# bluetooth_RGB.net
KiCad netlist of a schematic drawn in EAGLE
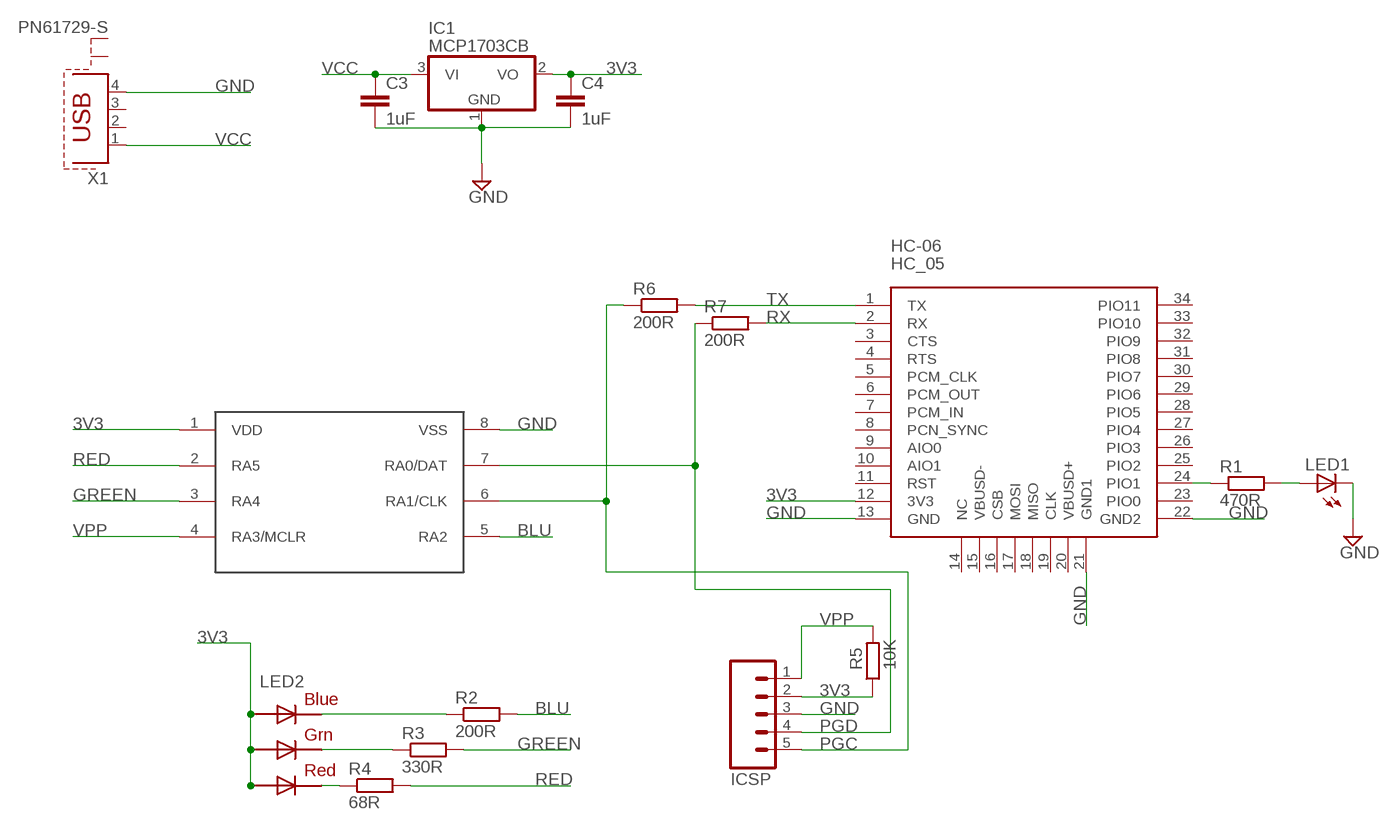
[diagram p0: schematic, sheet 1]

(export (version "E")
  (design (tool "Eeschema 10.0.6"))
  (components
    (comp (ref "C3")
      (value "1uF")
      (footprint "eagle-import:0805")
      (libsource (lib "eagle-import") (part "CAP0805"))
    )
    (comp (ref "C4")
      (value "1uF")
      (footprint "eagle-import:0805")
      (libsource (lib "eagle-import") (part "CAP0805"))
    )
    (comp (ref "HC-06")
      (value "HC_05")
      (footprint "eagle-import:BLUETOOTH_SMD")
      (libsource (lib "eagle-import") (part "HC_05"))
    )
    (comp (ref "IC1")
      (value "MCP1703CB")
      (footprint "eagle-import:SOT23")
      (libsource (lib "eagle-import") (part "MCP1703CB"))
    )
    (comp (ref "ICSP")
      (value "M05PTH")
      (footprint "eagle-import:1X05")
      (libsource (lib "eagle-import") (part "M05PTH"))
    )
    (comp (ref "LED1")
      (value "LEDCHIPLED_0805")
      (footprint "eagle-import:CHIPLED_0805")
      (libsource (lib "eagle-import") (part "LEDCHIPLED_0805"))
    )
    (comp (ref "LED2")
      (value "RGBLED5050")
      (footprint "eagle-import:RGBLED5050")
      (libsource (lib "eagle-import") (part "RGBLED5050"))
    )
    (comp (ref "R1")
      (value "470R")
      (footprint "eagle-import:M0805")
      (libsource (lib "eagle-import") (part "R-EU_M0805"))
    )
    (comp (ref "R2")
      (value "200R")
      (footprint "eagle-import:M0805")
      (libsource (lib "eagle-import") (part "R-EU_M0805"))
    )
    (comp (ref "R3")
      (value "330R")
      (footprint "eagle-import:M0805")
      (libsource (lib "eagle-import") (part "R-EU_M0805"))
    )
    (comp (ref "R4")
      (value "68R")
      (footprint "eagle-import:M0805")
      (libsource (lib "eagle-import") (part "R-EU_M0805"))
    )
    (comp (ref "R5")
      (value "10K")
      (footprint "eagle-import:M0805")
      (libsource (lib "eagle-import") (part "R-EU_M0805"))
    )
    (comp (ref "R6")
      (value "200R")
      (footprint "eagle-import:R0805")
      (libsource (lib "eagle-import") (part "R-EU_R0805"))
    )
    (comp (ref "R7")
      (value "200R")
      (footprint "eagle-import:R0805")
      (libsource (lib "eagle-import") (part "R-EU_R0805"))
    )
    (comp (ref "U2")
      (value "PIC12F1572")
      (footprint "eagle-import:MSOP8")
      (libsource (lib "eagle-import") (part "PIC12F1572"))
    )
    (comp (ref "X1")
      (value "PN61729-S")
      (footprint "eagle-import:PN61729-S")
      (libsource (lib "eagle-import") (part "PN61729-S"))
    )
  )
  (nets
    (net (code "1") (name "/3V3") (class "Default")
      (node (ref "C4") (pin "1") (pinfunction "1_1") (pintype "passive"))
      (node (ref "HC-06") (pin "12") (pinfunction "3V3_12") (pintype "bidirectional"))
      (node (ref "IC1") (pin "2") (pinfunction "VO_2") (pintype "passive"))
      (node (ref "ICSP") (pin "2") (pinfunction "2_2") (pintype "passive"))
      (node (ref "LED2") (pin "1") (pinfunction "GREEN_A_1") (pintype "bidirectional"))
      (node (ref "LED2") (pin "2") (pinfunction "RED_A_2") (pintype "bidirectional"))
      (node (ref "LED2") (pin "3") (pinfunction "BLUE_A_3") (pintype "bidirectional"))
      (node (ref "R5") (pin "1") (pinfunction "1_1") (pintype "passive"))
      (node (ref "U2") (pin "1") (pinfunction "VDD_1") (pintype "bidirectional"))
    )
    (net (code "2") (name "/BLU") (class "Default")
      (node (ref "R2") (pin "2") (pinfunction "2_2") (pintype "passive"))
      (node (ref "U2") (pin "5") (pinfunction "RA2_5") (pintype "bidirectional"))
    )
    (net (code "3") (name "/GREEN") (class "Default")
      (node (ref "R3") (pin "2") (pinfunction "2_2") (pintype "passive"))
      (node (ref "U2") (pin "3") (pinfunction "RA4_3") (pintype "bidirectional"))
    )
    (net (code "4") (name "/PGC") (class "Default")
      (node (ref "ICSP") (pin "5") (pinfunction "5_5") (pintype "passive"))
      (node (ref "R6") (pin "1") (pinfunction "1_1") (pintype "passive"))
      (node (ref "U2") (pin "6") (pinfunction "RA1/CLK_6") (pintype "bidirectional"))
    )
    (net (code "5") (name "/PGD") (class "Default")
      (node (ref "ICSP") (pin "4") (pinfunction "4_4") (pintype "passive"))
      (node (ref "R7") (pin "1") (pinfunction "1_1") (pintype "passive"))
      (node (ref "U2") (pin "7") (pinfunction "RA0/DAT_7") (pintype "bidirectional"))
    )
    (net (code "6") (name "/RED") (class "Default")
      (node (ref "R4") (pin "2") (pinfunction "2_2") (pintype "passive"))
      (node (ref "U2") (pin "2") (pinfunction "RA5_2") (pintype "bidirectional"))
    )
    (net (code "7") (name "/RX") (class "Default")
      (node (ref "HC-06") (pin "2") (pinfunction "RX_2") (pintype "bidirectional"))
      (node (ref "R7") (pin "2") (pinfunction "2_2") (pintype "passive"))
    )
    (net (code "8") (name "/TX") (class "Default")
      (node (ref "HC-06") (pin "1") (pinfunction "TX_1") (pintype "bidirectional"))
      (node (ref "R6") (pin "2") (pinfunction "2_2") (pintype "passive"))
    )
    (net (code "9") (name "/VCC") (class "Default")
      (node (ref "C3") (pin "1") (pinfunction "1_1") (pintype "passive"))
      (node (ref "IC1") (pin "3") (pinfunction "VI_3") (pintype "input"))
      (node (ref "X1") (pin "1") (pinfunction "1_1") (pintype "passive"))
    )
    (net (code "10") (name "/VPP") (class "Default")
      (node (ref "ICSP") (pin "1") (pinfunction "1_1") (pintype "passive"))
      (node (ref "R5") (pin "2") (pinfunction "2_2") (pintype "passive"))
      (node (ref "U2") (pin "4") (pinfunction "RA3/MCLR_4") (pintype "bidirectional"))
    )
    (net (code "11") (name "GND") (class "Default")
      (node (ref "C3") (pin "2") (pinfunction "2_2") (pintype "passive"))
      (node (ref "C4") (pin "2") (pinfunction "2_2") (pintype "passive"))
      (node (ref "HC-06") (pin "13") (pinfunction "GND_13") (pintype "bidirectional"))
      (node (ref "HC-06") (pin "21") (pinfunction "GND1_21") (pintype "bidirectional"))
      (node (ref "HC-06") (pin "22") (pinfunction "GND2_22") (pintype "bidirectional"))
      (node (ref "IC1") (pin "1") (pinfunction "GND_1") (pintype "passive"))
      (node (ref "ICSP") (pin "3") (pinfunction "3_3") (pintype "passive"))
      (node (ref "LED1") (pin "C") (pinfunction "C_C") (pintype "passive"))
      (node (ref "U2") (pin "8") (pinfunction "VSS_8") (pintype "bidirectional"))
      (node (ref "X1") (pin "4") (pinfunction "4_4") (pintype "passive"))
    )
    (net (code "12") (name "Net-(HC-06-PIO1)") (class "Default")
      (node (ref "HC-06") (pin "24") (pinfunction "PIO1_24") (pintype "bidirectional"))
      (node (ref "R1") (pin "1") (pinfunction "1_1") (pintype "passive"))
    )
    (net (code "13") (name "Net-(LED1-PadA)") (class "Default")
      (node (ref "LED1") (pin "A") (pinfunction "A_A") (pintype "passive"))
      (node (ref "R1") (pin "2") (pinfunction "2_2") (pintype "passive"))
    )
    (net (code "14") (name "Net-(LED2-BLUE_C)") (class "Default")
      (node (ref "LED2") (pin "4") (pinfunction "BLUE_C_4") (pintype "bidirectional"))
      (node (ref "R2") (pin "1") (pinfunction "1_1") (pintype "passive"))
    )
    (net (code "15") (name "Net-(LED2-GREEN_C)") (class "Default")
      (node (ref "LED2") (pin "6") (pinfunction "GREEN_C_6") (pintype "bidirectional"))
      (node (ref "R3") (pin "1") (pinfunction "1_1") (pintype "passive"))
    )
    (net (code "16") (name "Net-(LED2-RED_C)") (class "Default")
      (node (ref "LED2") (pin "5") (pinfunction "RED_C_5") (pintype "bidirectional"))
      (node (ref "R4") (pin "1") (pinfunction "1_1") (pintype "passive"))
    )
    (net (code "17") (name "unconnected-(HC-06-AIO0-Pad9)") (class "Default")
      (node (ref "HC-06") (pin "9") (pinfunction "AIO0_9") (pintype "bidirectional"))
    )
    (net (code "18") (name "unconnected-(HC-06-AIO1-Pad10)") (class "Default")
      (node (ref "HC-06") (pin "10") (pinfunction "AIO1_10") (pintype "bidirectional"))
    )
    (net (code "19") (name "unconnected-(HC-06-CLK-Pad19)") (class "Default")
      (node (ref "HC-06") (pin "19") (pinfunction "CLK_19") (pintype "bidirectional"))
    )
    (net (code "20") (name "unconnected-(HC-06-CSB-Pad16)") (class "Default")
      (node (ref "HC-06") (pin "16") (pinfunction "CSB_16") (pintype "bidirectional"))
    )
    (net (code "21") (name "unconnected-(HC-06-CTS-Pad3)") (class "Default")
      (node (ref "HC-06") (pin "3") (pinfunction "CTS_3") (pintype "bidirectional"))
    )
    (net (code "22") (name "unconnected-(HC-06-MISO-Pad18)") (class "Default")
      (node (ref "HC-06") (pin "18") (pinfunction "MISO_18") (pintype "bidirectional"))
    )
    (net (code "23") (name "unconnected-(HC-06-MOSI-Pad17)") (class "Default")
      (node (ref "HC-06") (pin "17") (pinfunction "MOSI_17") (pintype "bidirectional"))
    )
    (net (code "24") (name "unconnected-(HC-06-NC-Pad14)") (class "Default")
      (node (ref "HC-06") (pin "14") (pinfunction "NC_14") (pintype "bidirectional"))
    )
    (net (code "25") (name "unconnected-(HC-06-PCM_CLK-Pad5)") (class "Default")
      (node (ref "HC-06") (pin "5") (pinfunction "PCM_CLK_5") (pintype "bidirectional"))
    )
    (net (code "26") (name "unconnected-(HC-06-PCM_IN-Pad7)") (class "Default")
      (node (ref "HC-06") (pin "7") (pinfunction "PCM_IN_7") (pintype "bidirectional"))
    )
    (net (code "27") (name "unconnected-(HC-06-PCM_OUT-Pad6)") (class "Default")
      (node (ref "HC-06") (pin "6") (pinfunction "PCM_OUT_6") (pintype "bidirectional"))
    )
    (net (code "28") (name "unconnected-(HC-06-PCN_SYNC-Pad8)") (class "Default")
      (node (ref "HC-06") (pin "8") (pinfunction "PCN_SYNC_8") (pintype "bidirectional"))
    )
    (net (code "29") (name "unconnected-(HC-06-PIO0-Pad23)") (class "Default")
      (node (ref "HC-06") (pin "23") (pinfunction "PIO0_23") (pintype "bidirectional"))
    )
    (net (code "30") (name "unconnected-(HC-06-PIO2-Pad25)") (class "Default")
      (node (ref "HC-06") (pin "25") (pinfunction "PIO2_25") (pintype "bidirectional"))
    )
    (net (code "31") (name "unconnected-(HC-06-PIO3-Pad26)") (class "Default")
      (node (ref "HC-06") (pin "26") (pinfunction "PIO3_26") (pintype "bidirectional"))
    )
    (net (code "32") (name "unconnected-(HC-06-PIO4-Pad27)") (class "Default")
      (node (ref "HC-06") (pin "27") (pinfunction "PIO4_27") (pintype "bidirectional"))
    )
    (net (code "33") (name "unconnected-(HC-06-PIO5-Pad28)") (class "Default")
      (node (ref "HC-06") (pin "28") (pinfunction "PIO5_28") (pintype "bidirectional"))
    )
    (net (code "34") (name "unconnected-(HC-06-PIO6-Pad29)") (class "Default")
      (node (ref "HC-06") (pin "29") (pinfunction "PIO6_29") (pintype "bidirectional"))
    )
    (net (code "35") (name "unconnected-(HC-06-PIO7-Pad30)") (class "Default")
      (node (ref "HC-06") (pin "30") (pinfunction "PIO7_30") (pintype "bidirectional"))
    )
    (net (code "36") (name "unconnected-(HC-06-PIO8-Pad31)") (class "Default")
      (node (ref "HC-06") (pin "31") (pinfunction "PIO8_31") (pintype "bidirectional"))
    )
    (net (code "37") (name "unconnected-(HC-06-PIO9-Pad32)") (class "Default")
      (node (ref "HC-06") (pin "32") (pinfunction "PIO9_32") (pintype "bidirectional"))
    )
    (net (code "38") (name "unconnected-(HC-06-PIO10-Pad33)") (class "Default")
      (node (ref "HC-06") (pin "33") (pinfunction "PIO10_33") (pintype "bidirectional"))
    )
    (net (code "39") (name "unconnected-(HC-06-PIO11-Pad34)") (class "Default")
      (node (ref "HC-06") (pin "34") (pinfunction "PIO11_34") (pintype "bidirectional"))
    )
    (net (code "40") (name "unconnected-(HC-06-RST-Pad11)") (class "Default")
      (node (ref "HC-06") (pin "11") (pinfunction "RST_11") (pintype "bidirectional"))
    )
    (net (code "41") (name "unconnected-(HC-06-RTS-Pad4)") (class "Default")
      (node (ref "HC-06") (pin "4") (pinfunction "RTS_4") (pintype "bidirectional"))
    )
    (net (code "42") (name "unconnected-(HC-06-VBUSD+-Pad20)") (class "Default")
      (node (ref "HC-06") (pin "20") (pinfunction "VBUSD+_20") (pintype "bidirectional"))
    )
    (net (code "43") (name "unconnected-(HC-06-VBUSD--Pad15)") (class "Default")
      (node (ref "HC-06") (pin "15") (pinfunction "VBUSD-_15") (pintype "bidirectional"))
    )
    (net (code "44") (name "unconnected-(X1-Pad2)") (class "Default")
      (node (ref "X1") (pin "2") (pinfunction "2_2") (pintype "passive"))
    )
    (net (code "45") (name "unconnected-(X1-Pad3)") (class "Default")
      (node (ref "X1") (pin "3") (pinfunction "3_3") (pintype "passive"))
    )
    (net (code "46") (name "unconnected-(X1-PadS1)") (class "Default")
      (node (ref "X1") (pin "S1") (pinfunction "S1_S1") (pintype "passive"))
    )
    (net (code "47") (name "unconnected-(X1-PadS2)") (class "Default")
      (node (ref "X1") (pin "S2") (pinfunction "S2_S2") (pintype "passive"))
    )
  )
)
